# RMII.net
KiCad netlist of a schematic drawn in Altium Designer
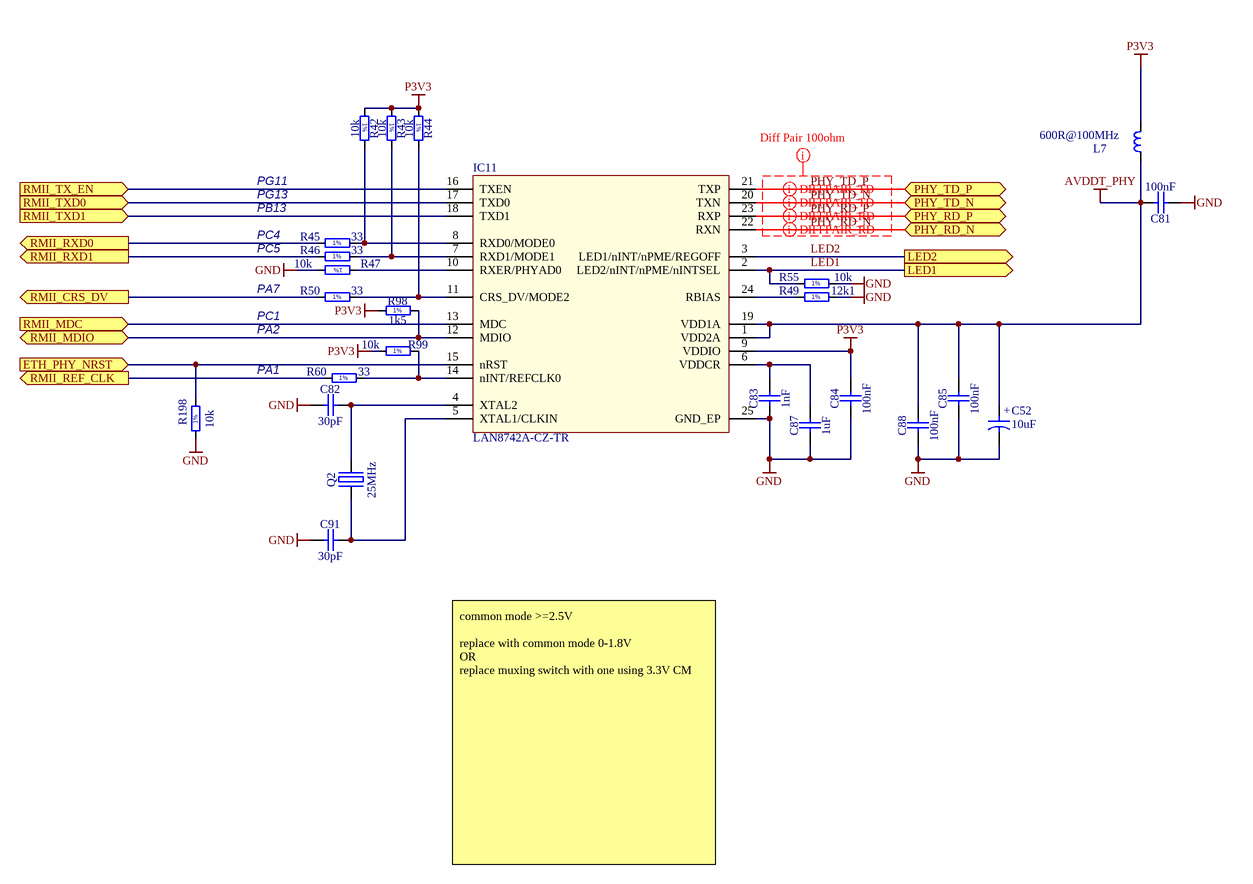
[diagram p0: RMII.SchDoc]

(export (version "E")
  (design (tool "Eeschema 10.0.6"))
  (components
    (comp (ref "C52")
      (value "10uF")
      (footprint "CAPMP3216X180N")
      (description "Polarised capacitor")
      (fields
        (field (name "PART NUMBER") "CTE3216-18_10UF_16V_20%_AVX_TCJ")
        (field (name "VOLTAGE") "16V")
        (field (name "AUTHOR") "CERN DEM JLC")
      )
      (libsource (lib "Capacitors") (part "Capacitor - polarized"))
    )
    (comp (ref "C81")
      (value "100nF")
      (footprint "CAPC1005X55N")
      (description "Non-polarised capacitor")
      (fields
        (field (name "PART NUMBER") "CC0402_100NF_16V_10%_X5R")
        (field (name "VOLTAGE") "16V")
        (field (name "AUTHOR") "CERN DEM JLC")
      )
      (libsource (lib "Capacitors") (part "Capacitor - non polarized"))
    )
    (comp (ref "C82")
      (value "30pF")
      (footprint "CAPC1005X55N")
      (description "Non-polarised capacitor")
      (fields
        (field (name "PART NUMBER") "CC0402_30PF_50V_1%_C0G_MURATA_GJM1555C1H300FB01")
        (field (name "VOLTAGE") "50V")
        (field (name "AUTHOR") "CERN DEM BC")
      )
      (libsource (lib "Capacitors") (part "Capacitor - non polarized"))
    )
    (comp (ref "C83")
      (value "1nF")
      (footprint "CAPC1005X55N")
      (description "Non-polarised capacitor")
      (fields
        (field (name "PART NUMBER") "CC0402_1NF_50V_10%_X7R")
        (field (name "VOLTAGE") "50V")
        (field (name "AUTHOR") "CERN DEM JLC")
      )
      (libsource (lib "Capacitors") (part "Capacitor - non polarized"))
    )
    (comp (ref "C84")
      (value "100nF")
      (footprint "CAPC1005X55N")
      (description "Non-polarised capacitor")
      (fields
        (field (name "PART NUMBER") "CC0402_100NF_16V_10%_X5R")
        (field (name "VOLTAGE") "16V")
        (field (name "AUTHOR") "CERN DEM JLC")
      )
      (libsource (lib "Capacitors") (part "Capacitor - non polarized"))
    )
    (comp (ref "C85")
      (value "100nF")
      (footprint "CAPC1005X55N")
      (description "Non-polarised capacitor")
      (fields
        (field (name "PART NUMBER") "CC0402_100NF_16V_10%_X5R")
        (field (name "VOLTAGE") "16V")
        (field (name "AUTHOR") "CERN DEM JLC")
      )
      (libsource (lib "Capacitors") (part "Capacitor - non polarized"))
    )
    (comp (ref "C87")
      (value "1uF")
      (footprint "CAPC1608X87N")
      (description "Non-polarised capacitor")
      (fields
        (field (name "PART NUMBER") "CC0603_1UF_16V_10%_X7R")
        (field (name "VOLTAGE") "16V")
        (field (name "AUTHOR") "CERN DEM JLC")
      )
      (libsource (lib "Capacitors") (part "Capacitor - non polarized"))
    )
    (comp (ref "C88")
      (value "100nF")
      (footprint "CAPC1005X55N")
      (description "Non-polarised capacitor")
      (fields
        (field (name "PART NUMBER") "CC0402_100NF_16V_10%_X5R")
        (field (name "VOLTAGE") "16V")
        (field (name "AUTHOR") "CERN DEM JLC")
      )
      (libsource (lib "Capacitors") (part "Capacitor - non polarized"))
    )
    (comp (ref "C91")
      (value "30pF")
      (footprint "CAPC1005X55N")
      (description "Non-polarised capacitor")
      (fields
        (field (name "PART NUMBER") "CC0402_30PF_50V_1%_C0G_MURATA_GJM1555C1H300FB01")
        (field (name "VOLTAGE") "50V")
        (field (name "AUTHOR") "CERN DEM BC")
      )
      (libsource (lib "Capacitors") (part "Capacitor - non polarized"))
    )
    (comp (ref "IC11")
      (value "LAN8742A-CZ-TR")
      (footprint "QFN24_0R5_4X4")
      (fields (field (name "MANUFACTURER") "MICROCHIP"))
      (libsource (lib "LIBRARY_SCH") (part "IFC_LAN8742A"))
    )
    (comp (ref "L7")
      (value "600R@100MHz")
      (footprint "INDC1005X55N")
      (description "Inductor")
      (fields
        (field (name "PART NUMBER") "IND0402_MURATA_BLM15HD601SN1")
        (field (name "POWER") "300mA")
        (field (name "AUTHOR") "CERN DEM JLC")
      )
      (libsource (lib "Inductors & Transformers") (part "Inductor"))
    )
    (comp (ref "Q2")
      (value "25MHz")
      (footprint "XTAL_ABRACON_ABLS")
      (description "Quartz Crystal")
      (fields
        (field (name "PART NUMBER") "XTAL_25MHZ_ABRACON_ABLS-25.000MHZ-B2F-T")
        (field (name "MANUFACTURER") "ABRACON")
        (field (name "AUTHOR") "CERN DEM JLC")
      )
      (libsource (lib "ICs And Semiconductors") (part "Quartz Crystal"))
    )
    (comp (ref "R42")
      (value "10k")
      (footprint "RESC1005X40N")
      (description "Resistor - 1%")
      (fields
        (field (name "PART NUMBER") "R0402_10K_1%_0.0625W_100PPM")
        (field (name "POWER") "0.0625W")
        (field (name "AUTHOR") "CERN DEM JLC")
      )
      (libsource (lib "Resistors") (part "Resistor - 1%"))
    )
    (comp (ref "R43")
      (value "10k")
      (footprint "RESC1005X40N")
      (description "Resistor - 1%")
      (fields
        (field (name "PART NUMBER") "R0402_10K_1%_0.0625W_100PPM")
        (field (name "POWER") "0.0625W")
        (field (name "AUTHOR") "CERN DEM JLC")
      )
      (libsource (lib "Resistors") (part "Resistor - 1%"))
    )
    (comp (ref "R44")
      (value "10k")
      (footprint "RESC1005X40N")
      (description "Resistor - 1%")
      (fields
        (field (name "PART NUMBER") "R0402_10K_1%_0.0625W_100PPM")
        (field (name "POWER") "0.0625W")
        (field (name "AUTHOR") "CERN DEM JLC")
      )
      (libsource (lib "Resistors") (part "Resistor - 1%"))
    )
    (comp (ref "R45")
      (value "33")
      (footprint "RESC1005X40N")
      (description "Resistor - 1%")
      (fields
        (field (name "PART NUMBER") "R0402_33R_1%_0.0625W_100PPM")
        (field (name "POWER") "0.0625W")
        (field (name "AUTHOR") "CERN DEM JLC")
      )
      (libsource (lib "Resistors") (part "Resistor - 1%"))
    )
    (comp (ref "R46")
      (value "33")
      (footprint "RESC1005X40N")
      (description "Resistor - 1%")
      (fields
        (field (name "PART NUMBER") "R0402_33R_1%_0.0625W_100PPM")
        (field (name "POWER") "0.0625W")
        (field (name "AUTHOR") "CERN DEM JLC")
      )
      (libsource (lib "Resistors") (part "Resistor - 1%"))
    )
    (comp (ref "R47")
      (value "10k")
      (footprint "RESC1005X40N")
      (description "Resistor - 1%")
      (fields
        (field (name "PART NUMBER") "R0402_10K_1%_0.0625W_100PPM")
        (field (name "POWER") "0.0625W")
        (field (name "AUTHOR") "CERN DEM JLC")
      )
      (libsource (lib "Resistors") (part "Resistor - 1%"))
    )
    (comp (ref "R49")
      (value "12k1")
      (footprint "RESC1005X40N")
      (description "Resistor - 1%")
      (fields
        (field (name "PART NUMBER") "R0402_12K1_1%_0.0625W_100PPM")
        (field (name "POWER") "0.0625W")
        (field (name "AUTHOR") "CERN DEM JLC")
      )
      (libsource (lib "Resistors") (part "Resistor - 1%"))
    )
    (comp (ref "R50")
      (value "33")
      (footprint "RESC1005X40N")
      (description "Resistor - 1%")
      (fields
        (field (name "PART NUMBER") "R0402_33R_1%_0.0625W_100PPM")
        (field (name "POWER") "0.0625W")
        (field (name "AUTHOR") "CERN DEM JLC")
      )
      (libsource (lib "Resistors") (part "Resistor - 1%"))
    )
    (comp (ref "R55")
      (value "10k")
      (footprint "RESC1005X40N")
      (description "Resistor - 1%")
      (fields
        (field (name "PART NUMBER") "R0402_10K_1%_0.0625W_100PPM")
        (field (name "POWER") "0.0625W")
        (field (name "AUTHOR") "CERN DEM JLC")
      )
      (libsource (lib "Resistors") (part "Resistor - 1%"))
    )
    (comp (ref "R60")
      (value "33")
      (footprint "RESC1005X40N")
      (description "Resistor - 1%")
      (fields
        (field (name "PART NUMBER") "R0402_33R_1%_0.0625W_100PPM")
        (field (name "POWER") "0.0625W")
        (field (name "AUTHOR") "CERN DEM JLC")
      )
      (libsource (lib "Resistors") (part "Resistor - 1%"))
    )
    (comp (ref "R98")
      (value "1k5")
      (footprint "RESC1005X40N")
      (description "Resistor - 1%")
      (fields
        (field (name "PART NUMBER") "R0402_1K5_1%_0.0625W_100PPM")
        (field (name "POWER") "0.0625W")
        (field (name "AUTHOR") "CERN DEM JLC")
      )
      (libsource (lib "Resistors") (part "Resistor - 1%"))
    )
    (comp (ref "R99")
      (value "10k")
      (footprint "RESC1005X40N")
      (description "Resistor - 1%")
      (fields
        (field (name "PART NUMBER") "R0402_10K_1%_0.0625W_100PPM")
        (field (name "POWER") "0.0625W")
        (field (name "AUTHOR") "CERN DEM JLC")
      )
      (libsource (lib "Resistors") (part "Resistor - 1%"))
    )
    (comp (ref "R198")
      (value "10k")
      (footprint "RESC1005X40N")
      (description "Resistor - 1%")
      (fields
        (field (name "PART NUMBER") "R0402_10K_1%_0.0625W_100PPM")
        (field (name "POWER") "0.0625W")
        (field (name "AUTHOR") "CERN DEM JLC")
      )
      (libsource (lib "Resistors") (part "Resistor - 1%"))
    )
  )
  (nets
    (net (code "1") (name "/ETH_PHY_NRST") (class "Default")
      (node (ref "IC11") (pin "15") (pinfunction "nRST_15") (pintype "passive"))
      (node (ref "R198") (pin "2") (pinfunction "2_2") (pintype "passive"))
    )
    (net (code "2") (name "/LED1") (class "Default")
      (node (ref "IC11") (pin "2") (pinfunction "LED2/nINT/nPME/nINTSEL_2") (pintype "passive"))
      (node (ref "R55") (pin "1") (pinfunction "1_1") (pintype "passive"))
    )
    (net (code "3") (name "/LED2") (class "Default")
      (node (ref "IC11") (pin "3") (pinfunction "LED1/nINT/nPME/REGOFF_3") (pintype "passive"))
    )
    (net (code "4") (name "/PHY_RD_N") (class "Default")
      (node (ref "IC11") (pin "22") (pinfunction "RXN_22") (pintype "passive"))
    )
    (net (code "5") (name "/PHY_RD_P") (class "Default")
      (node (ref "IC11") (pin "23") (pinfunction "RXP_23") (pintype "passive"))
    )
    (net (code "6") (name "/PHY_TD_N") (class "Default")
      (node (ref "IC11") (pin "20") (pinfunction "TXN_20") (pintype "passive"))
    )
    (net (code "7") (name "/PHY_TD_P") (class "Default")
      (node (ref "IC11") (pin "21") (pinfunction "TXP_21") (pintype "passive"))
    )
    (net (code "8") (name "/RMII_CRS_DV") (class "Default")
      (node (ref "R50") (pin "1") (pinfunction "1_1") (pintype "passive"))
    )
    (net (code "9") (name "/RMII_MDC") (class "Default")
      (node (ref "IC11") (pin "13") (pinfunction "MDC_13") (pintype "passive"))
    )
    (net (code "10") (name "/RMII_MDIO") (class "Default")
      (node (ref "IC11") (pin "12") (pinfunction "MDIO_12") (pintype "passive"))
      (node (ref "R98") (pin "2") (pinfunction "2_2") (pintype "passive"))
    )
    (net (code "11") (name "/RMII_REF_CLK") (class "Default")
      (node (ref "R60") (pin "1") (pinfunction "1_1") (pintype "passive"))
    )
    (net (code "12") (name "/RMII_RXD0") (class "Default")
      (node (ref "R45") (pin "1") (pinfunction "1_1") (pintype "passive"))
    )
    (net (code "13") (name "/RMII_RXD1") (class "Default")
      (node (ref "R46") (pin "1") (pinfunction "1_1") (pintype "passive"))
    )
    (net (code "14") (name "/RMII_TXD0") (class "Default")
      (node (ref "IC11") (pin "17") (pinfunction "TXD0_17") (pintype "passive"))
    )
    (net (code "15") (name "/RMII_TXD1") (class "Default")
      (node (ref "IC11") (pin "18") (pinfunction "TXD1_18") (pintype "passive"))
    )
    (net (code "16") (name "/RMII_TX_EN") (class "Default")
      (node (ref "IC11") (pin "16") (pinfunction "TXEN_16") (pintype "passive"))
    )
    (net (code "17") (name "AVDDT_PHY") (class "Default")
      (node (ref "C52") (pin "1") (pinfunction "1_1") (pintype "passive"))
      (node (ref "C81") (pin "2") (pinfunction "2_2") (pintype "passive"))
      (node (ref "C85") (pin "2") (pinfunction "2_2") (pintype "passive"))
      (node (ref "C88") (pin "2") (pinfunction "2_2") (pintype "passive"))
      (node (ref "IC11") (pin "1") (pinfunction "VDD2A_1") (pintype "passive"))
      (node (ref "IC11") (pin "19") (pinfunction "VDD1A_19") (pintype "passive"))
      (node (ref "L7") (pin "1") (pinfunction "1_1") (pintype "passive"))
    )
    (net (code "18") (name "GND") (class "Default")
      (node (ref "C52") (pin "2") (pinfunction "2_2") (pintype "passive"))
      (node (ref "C81") (pin "1") (pinfunction "1_1") (pintype "passive"))
      (node (ref "C82") (pin "1") (pinfunction "1_1") (pintype "passive"))
      (node (ref "C83") (pin "1") (pinfunction "1_1") (pintype "passive"))
      (node (ref "C84") (pin "1") (pinfunction "1_1") (pintype "passive"))
      (node (ref "C85") (pin "1") (pinfunction "1_1") (pintype "passive"))
      (node (ref "C87") (pin "1") (pinfunction "1_1") (pintype "passive"))
      (node (ref "C88") (pin "1") (pinfunction "1_1") (pintype "passive"))
      (node (ref "C91") (pin "1") (pinfunction "1_1") (pintype "passive"))
      (node (ref "IC11") (pin "25") (pinfunction "GND_EP_25") (pintype "passive"))
      (node (ref "R198") (pin "1") (pinfunction "1_1") (pintype "passive"))
      (node (ref "R47") (pin "2") (pinfunction "2_2") (pintype "passive"))
      (node (ref "R49") (pin "2") (pinfunction "2_2") (pintype "passive"))
      (node (ref "R55") (pin "2") (pinfunction "2_2") (pintype "passive"))
    )
    (net (code "19") (name "Net-(IC11-CRS_DV{slash}MODE2)") (class "Default")
      (node (ref "IC11") (pin "11") (pinfunction "CRS_DV/MODE2_11") (pintype "passive"))
      (node (ref "R44") (pin "2") (pinfunction "2_2") (pintype "passive"))
      (node (ref "R50") (pin "2") (pinfunction "2_2") (pintype "passive"))
    )
    (net (code "20") (name "Net-(IC11-RBIAS)") (class "Default")
      (node (ref "IC11") (pin "24") (pinfunction "RBIAS_24") (pintype "passive"))
      (node (ref "R49") (pin "1") (pinfunction "1_1") (pintype "passive"))
    )
    (net (code "21") (name "Net-(IC11-RXD0{slash}MODE0)") (class "Default")
      (node (ref "IC11") (pin "8") (pinfunction "RXD0/MODE0_8") (pintype "passive"))
      (node (ref "R42") (pin "2") (pinfunction "2_2") (pintype "passive"))
      (node (ref "R45") (pin "2") (pinfunction "2_2") (pintype "passive"))
    )
    (net (code "22") (name "Net-(IC11-RXD1{slash}MODE1)") (class "Default")
      (node (ref "IC11") (pin "7") (pinfunction "RXD1/MODE1_7") (pintype "passive"))
      (node (ref "R43") (pin "2") (pinfunction "2_2") (pintype "passive"))
      (node (ref "R46") (pin "2") (pinfunction "2_2") (pintype "passive"))
    )
    (net (code "23") (name "Net-(IC11-RXER{slash}PHYAD0)") (class "Default")
      (node (ref "IC11") (pin "10") (pinfunction "RXER/PHYAD0_10") (pintype "passive"))
      (node (ref "R47") (pin "1") (pinfunction "1_1") (pintype "passive"))
    )
    (net (code "24") (name "Net-(IC11-VDDCR)") (class "Default")
      (node (ref "C83") (pin "2") (pinfunction "2_2") (pintype "passive"))
      (node (ref "C87") (pin "2") (pinfunction "2_2") (pintype "passive"))
      (node (ref "IC11") (pin "6") (pinfunction "VDDCR_6") (pintype "passive"))
    )
    (net (code "25") (name "Net-(IC11-XTAL1{slash}CLKIN)") (class "Default")
      (node (ref "C91") (pin "2") (pinfunction "2_2") (pintype "passive"))
      (node (ref "IC11") (pin "5") (pinfunction "XTAL1/CLKIN_5") (pintype "passive"))
      (node (ref "Q2") (pin "1") (pinfunction "OSC1_1") (pintype "passive"))
    )
    (net (code "26") (name "Net-(IC11-XTAL2)") (class "Default")
      (node (ref "C82") (pin "2") (pinfunction "2_2") (pintype "passive"))
      (node (ref "IC11") (pin "4") (pinfunction "XTAL2_4") (pintype "passive"))
      (node (ref "Q2") (pin "2") (pinfunction "OSC2_2") (pintype "passive"))
    )
    (net (code "27") (name "Net-(IC11-nINT{slash}REFCLK0)") (class "Default")
      (node (ref "IC11") (pin "14") (pinfunction "nINT/REFCLK0_14") (pintype "passive"))
      (node (ref "R60") (pin "2") (pinfunction "2_2") (pintype "passive"))
      (node (ref "R99") (pin "2") (pinfunction "2_2") (pintype "passive"))
    )
    (net (code "28") (name "P3V3") (class "Default")
      (node (ref "C84") (pin "2") (pinfunction "2_2") (pintype "passive"))
      (node (ref "IC11") (pin "9") (pinfunction "VDDIO_9") (pintype "passive"))
      (node (ref "L7") (pin "2") (pinfunction "2_2") (pintype "passive"))
      (node (ref "R42") (pin "1") (pinfunction "1_1") (pintype "passive"))
      (node (ref "R43") (pin "1") (pinfunction "1_1") (pintype "passive"))
      (node (ref "R44") (pin "1") (pinfunction "1_1") (pintype "passive"))
      (node (ref "R98") (pin "1") (pinfunction "1_1") (pintype "passive"))
      (node (ref "R99") (pin "1") (pinfunction "1_1") (pintype "passive"))
    )
  )
)
